# SHTC3_Breakout.net
KiCad netlist of a schematic drawn in EAGLE
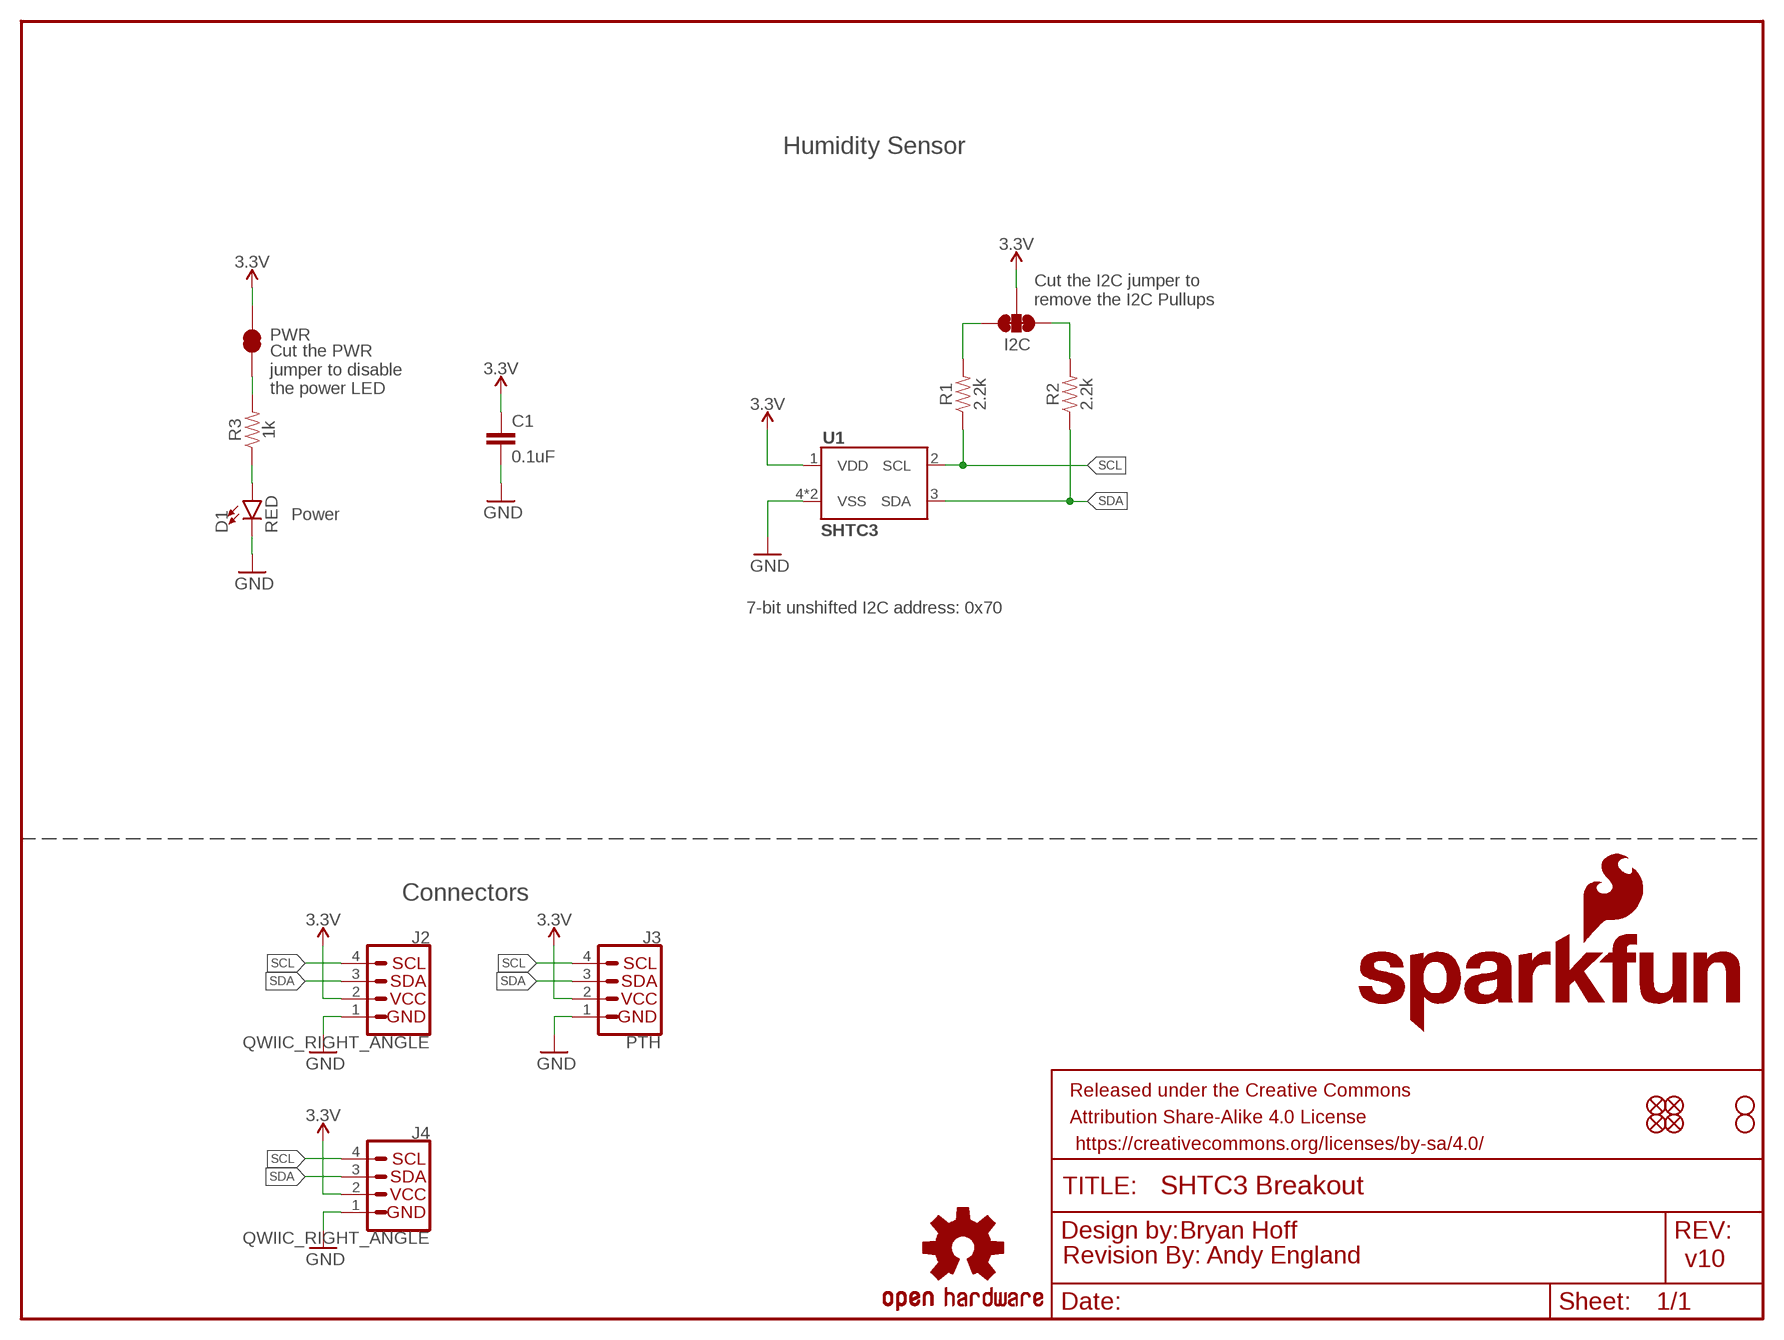
[diagram p0: schematic, sheet 1]

(export (version "E")
  (design (tool "Eeschema 10.0.6"))
  (components
    (comp (ref "C1")
      (value "0.1uF")
      (footprint "eagle-import:0603")
      (libsource (lib "eagle-import") (part "0.1UF-0603-25V-(+80/-20%)"))
    )
    (comp (ref "D1")
      (value "RED")
      (footprint "eagle-import:LED-0603")
      (libsource (lib "eagle-import") (part "LED-RED0603"))
    )
    (comp (ref "FRAME1")
      (value "FRAME-LETTER")
      (footprint "eagle-import:CREATIVE_COMMONS")
      (libsource (lib "eagle-import") (part "FRAME-LETTER"))
    )
    (comp (ref "I2C")
      (value "JUMPER-SMT_3_2-NC_TRACE_SILK")
      (footprint "eagle-import:SMT-JUMPER_3_2-NC_TRACE_SILK")
      (libsource (lib "eagle-import") (part "JUMPER-SMT_3_2-NC_TRACE_SILK"))
    )
    (comp (ref "J2")
      (value "QWIIC_RIGHT_ANGLE")
      (footprint "eagle-import:JST04_1MM_RA")
      (libsource (lib "eagle-import") (part "QWIIC_CONNECTORJS-1MM"))
    )
    (comp (ref "J3")
      (value "PTH")
      (footprint "eagle-import:1X04_NO_SILK")
      (libsource (lib "eagle-import") (part "I2C_STANDARD_NO_SILK"))
    )
    (comp (ref "J4")
      (value "QWIIC_RIGHT_ANGLE")
      (footprint "eagle-import:JST04_1MM_RA")
      (libsource (lib "eagle-import") (part "QWIIC_CONNECTORJS-1MM"))
    )
    (comp (ref "JP1")
      (value "FIDUCIALUFIDUCIAL")
      (footprint "eagle-import:MICRO-FIDUCIAL")
      (libsource (lib "eagle-import") (part "FIDUCIALUFIDUCIAL"))
    )
    (comp (ref "JP2")
      (value "FIDUCIALUFIDUCIAL")
      (footprint "eagle-import:MICRO-FIDUCIAL")
      (libsource (lib "eagle-import") (part "FIDUCIALUFIDUCIAL"))
    )
    (comp (ref "JP3")
      (value "STAND-OFF")
      (footprint "eagle-import:STAND-OFF")
      (libsource (lib "eagle-import") (part "STAND-OFF"))
    )
    (comp (ref "JP4")
      (value "STAND-OFF")
      (footprint "eagle-import:STAND-OFF")
      (libsource (lib "eagle-import") (part "STAND-OFF"))
    )
    (comp (ref "JP5")
      (value "FIDUCIALUFIDUCIAL")
      (footprint "eagle-import:MICRO-FIDUCIAL")
      (libsource (lib "eagle-import") (part "FIDUCIALUFIDUCIAL"))
    )
    (comp (ref "JP6")
      (value "FIDUCIALUFIDUCIAL")
      (footprint "eagle-import:MICRO-FIDUCIAL")
      (libsource (lib "eagle-import") (part "FIDUCIALUFIDUCIAL"))
    )
    (comp (ref "LOGO1")
      (value "OSHW-LOGOMINI")
      (footprint "eagle-import:OSHW-LOGO-MINI")
      (libsource (lib "eagle-import") (part "OSHW-LOGOMINI"))
    )
    (comp (ref "LOGO2")
      (value "SFE_LOGO_NAME_FLAME.1_INCH")
      (footprint "eagle-import:SFE_LOGO_NAME_FLAME_.1")
      (libsource (lib "eagle-import") (part "SFE_LOGO_NAME_FLAME.1_INCH"))
    )
    (comp (ref "LOGO3")
      (value "SFE_LOGO_NAME_FLAME.1_INCH")
      (footprint "eagle-import:SFE_LOGO_NAME_FLAME_.1")
      (libsource (lib "eagle-import") (part "SFE_LOGO_NAME_FLAME.1_INCH"))
    )
    (comp (ref "LOGO4")
      (value "REVISION")
      (footprint "eagle-import:REVISION")
      (libsource (lib "eagle-import") (part "REVISION"))
    )
    (comp (ref "PWR")
      (value "JUMPER-SMT_2_NC_TRACE_NO-SILK")
      (footprint "eagle-import:SMT-JUMPER_2_NC_TRACE_NO-SILK")
      (libsource (lib "eagle-import") (part "JUMPER-SMT_2_NC_TRACE_NO-SILK"))
    )
    (comp (ref "R1")
      (value "2.2k")
      (footprint "eagle-import:0603")
      (libsource (lib "eagle-import") (part "2.2KOHM-0603-1/10W-1%"))
    )
    (comp (ref "R2")
      (value "2.2k")
      (footprint "eagle-import:0603")
      (libsource (lib "eagle-import") (part "2.2KOHM-0603-1/10W-1%"))
    )
    (comp (ref "R3")
      (value "1k")
      (footprint "eagle-import:0603")
      (libsource (lib "eagle-import") (part "1KOHM-0603-1/10W-1%"))
    )
    (comp (ref "U1")
      (value "SHTC3")
      (footprint "eagle-import:SHTC3")
      (libsource (lib "eagle-import") (part "SHTC3"))
    )
  )
  (nets
    (net (code "1") (name "3.3V") (class "Default")
      (node (ref "C1") (pin "1") (pinfunction "1_1") (pintype "passive"))
      (node (ref "I2C") (pin "2") (pinfunction "2_2") (pintype "passive"))
      (node (ref "J2") (pin "2") (pinfunction "2_2") (pintype "power_in"))
      (node (ref "J3") (pin "2") (pinfunction "VCC_2") (pintype "power_in"))
      (node (ref "J4") (pin "2") (pinfunction "2_2") (pintype "power_in"))
      (node (ref "PWR") (pin "2") (pinfunction "2_2") (pintype "passive"))
      (node (ref "U1") (pin "1") (pinfunction "VDD_1") (pintype "bidirectional"))
    )
    (net (code "2") (name "GND") (class "Default")
      (node (ref "C1") (pin "2") (pinfunction "2_2") (pintype "passive"))
      (node (ref "D1") (pin "C") (pinfunction "C_C") (pintype "passive"))
      (node (ref "J2") (pin "1") (pinfunction "1_1") (pintype "power_in"))
      (node (ref "J3") (pin "1") (pinfunction "GND_1") (pintype "power_in"))
      (node (ref "J4") (pin "1") (pinfunction "1_1") (pintype "power_in"))
      (node (ref "U1") (pin "4") (pinfunction "VSS_4") (pintype "bidirectional"))
      (node (ref "U1") (pin "5") (pinfunction "VSS_5") (pintype "bidirectional"))
    )
    (net (code "3") (name "Net-(D1-PadA)") (class "Default")
      (node (ref "D1") (pin "A") (pinfunction "A_A") (pintype "passive"))
      (node (ref "R3") (pin "1") (pinfunction "1_1") (pintype "passive"))
    )
    (net (code "4") (name "Net-(I2C-Pad1)") (class "Default")
      (node (ref "I2C") (pin "1") (pinfunction "1_1") (pintype "passive"))
      (node (ref "R2") (pin "2") (pinfunction "2_2") (pintype "passive"))
    )
    (net (code "5") (name "Net-(I2C-Pad3)") (class "Default")
      (node (ref "I2C") (pin "3") (pinfunction "3_3") (pintype "passive"))
      (node (ref "R1") (pin "2") (pinfunction "2_2") (pintype "passive"))
    )
    (net (code "6") (name "Net-(PWR-Pad1)") (class "Default")
      (node (ref "PWR") (pin "1") (pinfunction "1_1") (pintype "passive"))
      (node (ref "R3") (pin "2") (pinfunction "2_2") (pintype "passive"))
    )
    (net (code "7") (name "SCL") (class "Default")
      (node (ref "J2") (pin "4") (pinfunction "4_4") (pintype "passive"))
      (node (ref "J3") (pin "4") (pinfunction "SCL_4") (pintype "passive"))
      (node (ref "J4") (pin "4") (pinfunction "4_4") (pintype "passive"))
      (node (ref "R1") (pin "1") (pinfunction "1_1") (pintype "passive"))
      (node (ref "U1") (pin "2") (pinfunction "SCL_2") (pintype "bidirectional"))
    )
    (net (code "8") (name "SDA") (class "Default")
      (node (ref "J2") (pin "3") (pinfunction "3_3") (pintype "passive"))
      (node (ref "J3") (pin "3") (pinfunction "SDA_3") (pintype "passive"))
      (node (ref "J4") (pin "3") (pinfunction "3_3") (pintype "passive"))
      (node (ref "R2") (pin "1") (pinfunction "1_1") (pintype "passive"))
      (node (ref "U1") (pin "3") (pinfunction "SDA_3") (pintype "bidirectional"))
    )
  )
)
